# 2_MCU.net
KiCad netlist of a schematic drawn in Altium Designer
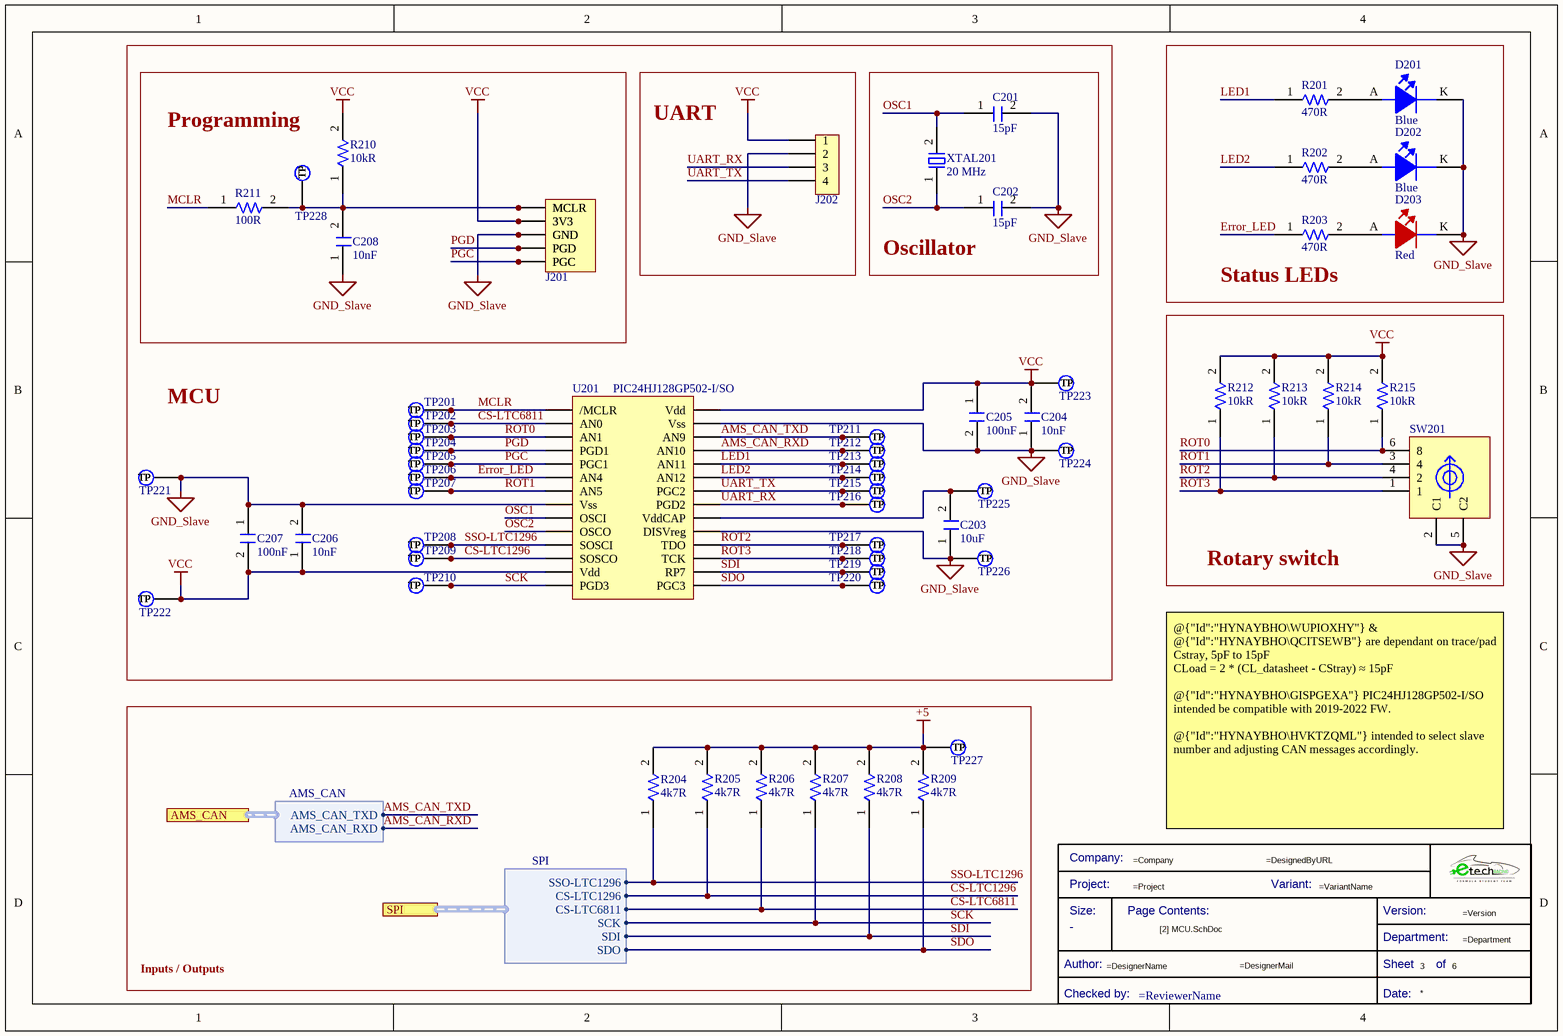
[diagram p0: [2] MCU.SchDoc]

(export (version "E")
  (design (tool "Eeschema 10.0.6"))
  (components
    (comp (ref "*")
      (value "Title Block_template")
      (description "Standard Title Block")
      (fields (field (name "SIZE") "-"))
      (libsource (lib "e-Tech_Racing") (part "Title Block_template"))
    )
    (comp (ref "C201")
      (value "885012007052")
      (footprint "C0805FNPC-R")
      (description "Cap, 15PF, 50V, 5%, C0G/NP0, 0805")
      (fields
        (field (name "TOLERANCE") "5%")
        (field (name "CAPACITANCE") "15pF")
        (field (name ".CREATOR") "DR")
      )
      (libsource (lib "Passives") (part "C15p-50V-0805FNPC-NP0"))
    )
    (comp (ref "C202")
      (value "885012007052")
      (footprint "C0805FNPC-R")
      (description "Cap, 15PF, 50V, 5%, C0G/NP0, 0805")
      (fields
        (field (name "TOLERANCE") "5%")
        (field (name "CAPACITANCE") "15pF")
        (field (name ".CREATOR") "DR")
      )
      (libsource (lib "Passives") (part "C15p-50V-0805FNPC-NP0"))
    )
    (comp (ref "C203")
      (value "885012107014")
      (footprint "C0805FNPC-R")
      (fields (field (name "TOLERANCE") "20%") (field (name "CAPACITANCE") "10uF"))
      (libsource (lib "Passives") (part "C10u-50V-0805FNPC-X7R"))
    )
    (comp (ref "C204")
      (value "885012207092")
      (footprint "C0805FNPC-R")
      (description "Cap, 0.01ΜF, 50V, 10%, X7R, 0805")
      (fields
        (field (name "TOLERANCE") "10%")
        (field (name "CAPACITANCE") "10nF")
        (field (name ".CREATOR") "DR")
      )
      (libsource (lib "Passives") (part "C10n-50V-0805FNPC-X7R"))
    )
    (comp (ref "C205")
      (value "885012207098")
      (footprint "C0805FNPC-R")
      (description "Cap, 0.1ΜF, 50V, 10%, X7R, 0805")
      (fields
        (field (name "TOLERANCE") "10%")
        (field (name "CAPACITANCE") "100nF")
        (field (name ".CREATOR") "DR")
      )
      (libsource (lib "Passives") (part "C100n-50V-0805FNPC-X7R"))
    )
    (comp (ref "C206")
      (value "885012207092")
      (footprint "C0805FNPC-R")
      (description "Cap, 0.01ΜF, 50V, 10%, X7R, 0805")
      (fields
        (field (name "TOLERANCE") "10%")
        (field (name "CAPACITANCE") "10nF")
        (field (name ".CREATOR") "DR")
      )
      (libsource (lib "Passives") (part "C10n-50V-0805FNPC-X7R"))
    )
    (comp (ref "C207")
      (value "885012207098")
      (footprint "C0805FNPC-R")
      (description "Cap, 0.1ΜF, 50V, 10%, X7R, 0805")
      (fields
        (field (name "TOLERANCE") "10%")
        (field (name "CAPACITANCE") "100nF")
        (field (name ".CREATOR") "DR")
      )
      (libsource (lib "Passives") (part "C100n-50V-0805FNPC-X7R"))
    )
    (comp (ref "C208")
      (value "885012207092")
      (footprint "C0805FNPC-R")
      (description "Cap, 0.01ΜF, 50V, 10%, X7R, 0805")
      (fields
        (field (name "TOLERANCE") "10%")
        (field (name "CAPACITANCE") "10nF")
        (field (name ".CREATOR") "DR")
      )
      (libsource (lib "Passives") (part "C10n-50V-0805FNPC-X7R"))
    )
    (comp (ref "D201")
      (value "150080BS75000")
      (footprint "LED_0805_WE")
      (description "LED BLUE CLEAR 0805 SMD")
      (fields (field (name "COLOR") "Blue") (field (name ".CREATOR") "GP"))
      (libsource (lib "Semiconductor") (part "LEDBS-0805-145"))
    )
    (comp (ref "D202")
      (value "150080BS75000")
      (footprint "LED_0805_WE")
      (description "LED BLUE CLEAR 0805 SMD")
      (fields (field (name "COLOR") "Blue") (field (name ".CREATOR") "GP"))
      (libsource (lib "Semiconductor") (part "LEDBS-0805-145"))
    )
    (comp (ref "D203")
      (value "150080RS75000")
      (footprint "LED_0805_WE")
      (description "0805(H=0.8mm) 红色 高亮 λD=625nm VF=2V IF=30mA PD=72mW")
      (fields (field (name "COLOR") "Red") (field (name ".CREATOR") "DR"))
      (libsource (lib "Semiconductor") (part "LEDRS-0805-150"))
    )
    (comp (ref "J201")
      (value "61300511121")
      (footprint "J_PinHeader_1x5")
      (description "THT Vertical Pin Header WR-PHD, Pitch 2.54 mm, Single Row, 5 pins")
      (fields (field (name "MANUFACTURER") "Molex") (field (name ".CREATOR") "GP"))
      (libsource (lib "Electromechanical") (part "J_Pickit3"))
    )
    (comp (ref "J202")
      (value "61300411121")
      (footprint "J_PinHeader_1x4")
      (description "CONN HEADER 4 POS 2.54")
      (fields (field (name ".CREATOR") "AC"))
      (libsource (lib "Electromechanical") (part "J_UART"))
    )
    (comp (ref "R201")
      (value "CR0805-FX-4700GLF")
      (footprint "R0805FTK")
      (description "Res Thick Film 0805 470 Ohm 1% 1/8W ±100ppm/°C Molded SMD SMD Paper Tape on Plastic Reel")
      (fields
        (field (name "TOLERANCE") "1%")
        (field (name "RESISTANCE") "470R")
        (field (name ".CREATOR") "DR")
      )
      (libsource (lib "Passives") (part "R470-0805FTK"))
    )
    (comp (ref "R202")
      (value "CR0805-FX-4700GLF")
      (footprint "R0805FTK")
      (description "Res Thick Film 0805 470 Ohm 1% 1/8W ±100ppm/°C Molded SMD SMD Paper Tape on Plastic Reel")
      (fields
        (field (name "TOLERANCE") "1%")
        (field (name "RESISTANCE") "470R")
        (field (name ".CREATOR") "DR")
      )
      (libsource (lib "Passives") (part "R470-0805FTK"))
    )
    (comp (ref "R203")
      (value "CR0805-FX-4700GLF")
      (footprint "R0805FTK")
      (description "Res Thick Film 0805 470 Ohm 1% 1/8W ±100ppm/°C Molded SMD SMD Paper Tape on Plastic Reel")
      (fields
        (field (name "TOLERANCE") "1%")
        (field (name "RESISTANCE") "470R")
        (field (name ".CREATOR") "DR")
      )
      (libsource (lib "Passives") (part "R470-0805FTK"))
    )
    (comp (ref "R204")
      (value "CR0805-JW-472ELF")
      (footprint "R0805FTK")
      (description "Res Thick Film 0805 4.7K Ohm 5% 1/8W ±200ppm/°C Molded SMD SMD Paper Tape on Plastic Reel")
      (fields
        (field (name "TOLERANCE") "5%")
        (field (name "RESISTANCE") "4k7R")
        (field (name ".CREATOR") "DR")
      )
      (libsource (lib "Passives") (part "R4.7K-0805FTK"))
    )
    (comp (ref "R205")
      (value "CR0805-JW-472ELF")
      (footprint "R0805FTK")
      (description "Res Thick Film 0805 4.7K Ohm 5% 1/8W ±200ppm/°C Molded SMD SMD Paper Tape on Plastic Reel")
      (fields
        (field (name "TOLERANCE") "5%")
        (field (name "RESISTANCE") "4k7R")
        (field (name ".CREATOR") "DR")
      )
      (libsource (lib "Passives") (part "R4.7K-0805FTK"))
    )
    (comp (ref "R206")
      (value "CR0805-JW-472ELF")
      (footprint "R0805FTK")
      (description "Res Thick Film 0805 4.7K Ohm 5% 1/8W ±200ppm/°C Molded SMD SMD Paper Tape on Plastic Reel")
      (fields
        (field (name "TOLERANCE") "5%")
        (field (name "RESISTANCE") "4k7R")
        (field (name ".CREATOR") "DR")
      )
      (libsource (lib "Passives") (part "R4.7K-0805FTK"))
    )
    (comp (ref "R207")
      (value "CR0805-JW-472ELF")
      (footprint "R0805FTK")
      (description "Res Thick Film 0805 4.7K Ohm 5% 1/8W ±200ppm/°C Molded SMD SMD Paper Tape on Plastic Reel")
      (fields
        (field (name "TOLERANCE") "5%")
        (field (name "RESISTANCE") "4k7R")
        (field (name ".CREATOR") "DR")
      )
      (libsource (lib "Passives") (part "R4.7K-0805FTK"))
    )
    (comp (ref "R208")
      (value "CR0805-JW-472ELF")
      (footprint "R0805FTK")
      (description "Res Thick Film 0805 4.7K Ohm 5% 1/8W ±200ppm/°C Molded SMD SMD Paper Tape on Plastic Reel")
      (fields
        (field (name "TOLERANCE") "5%")
        (field (name "RESISTANCE") "4k7R")
        (field (name ".CREATOR") "DR")
      )
      (libsource (lib "Passives") (part "R4.7K-0805FTK"))
    )
    (comp (ref "R209")
      (value "CR0805-JW-472ELF")
      (footprint "R0805FTK")
      (description "Res Thick Film 0805 4.7K Ohm 5% 1/8W ±200ppm/°C Molded SMD SMD Paper Tape on Plastic Reel")
      (fields
        (field (name "TOLERANCE") "5%")
        (field (name "RESISTANCE") "4k7R")
        (field (name ".CREATOR") "DR")
      )
      (libsource (lib "Passives") (part "R4.7K-0805FTK"))
    )
    (comp (ref "R210")
      (value "CR0805-JW-103ELF")
      (footprint "R0805FTK")
      (fields
        (field (name "TOLERANCE") "5%")
        (field (name "RESISTANCE") "10kR")
        (field (name ".CREATOR") "DR")
      )
      (libsource (lib "Passives") (part "R10k-0805FTK"))
    )
    (comp (ref "R211")
      (value "CR0805-FX-1000ELF")
      (footprint "R0805FTK")
      (description "Res Thick Film 0805 100 Ohm 1% 1/8W ±100ppm/°C Molded SMD SMD Paper Tape on Plastic Reel")
      (fields
        (field (name "TOLERANCE") "1%")
        (field (name "RESISTANCE") "100R")
        (field (name ".CREATOR") "DR")
      )
      (libsource (lib "Passives") (part "R100-0805FTK"))
    )
    (comp (ref "R212")
      (value "CR0805-JW-103ELF")
      (footprint "R0805FTK")
      (fields
        (field (name "TOLERANCE") "5%")
        (field (name "RESISTANCE") "10kR")
        (field (name ".CREATOR") "DR")
      )
      (libsource (lib "Passives") (part "R10k-0805FTK"))
    )
    (comp (ref "R213")
      (value "CR0805-JW-103ELF")
      (footprint "R0805FTK")
      (fields
        (field (name "TOLERANCE") "5%")
        (field (name "RESISTANCE") "10kR")
        (field (name ".CREATOR") "DR")
      )
      (libsource (lib "Passives") (part "R10k-0805FTK"))
    )
    (comp (ref "R214")
      (value "CR0805-JW-103ELF")
      (footprint "R0805FTK")
      (fields
        (field (name "TOLERANCE") "5%")
        (field (name "RESISTANCE") "10kR")
        (field (name ".CREATOR") "DR")
      )
      (libsource (lib "Passives") (part "R10k-0805FTK"))
    )
    (comp (ref "R215")
      (value "CR0805-JW-103ELF")
      (footprint "R0805FTK")
      (fields
        (field (name "TOLERANCE") "5%")
        (field (name "RESISTANCE") "10kR")
        (field (name ".CREATOR") "DR")
      )
      (libsource (lib "Passives") (part "R10k-0805FTK"))
    )
    (comp (ref "SW201")
      (value "428542320816")
      (footprint "16RotarySw")
      (description "Switch Rotary DIP Hex 100MA 42V")
      (fields (field (name ".CREATOR") "DR"))
      (libsource (lib "Electromechanical") (part "16RotarySwitch"))
    )
    (comp (ref "TP201")
      (value "TestPoint")
      (footprint "TestPoint")
      (description "Test Point 1x1 mm")
      (fields (field (name ".CREATOR") "GP") (field (name ".PCBCHECK") "GP") (field (name ".SCHCHECK") "GP"))
      (libsource (lib "e-Tech_Racing") (part "TestPoint"))
    )
    (comp (ref "TP202")
      (value "TestPoint")
      (footprint "TestPoint")
      (description "Test Point 1x1 mm")
      (fields (field (name ".CREATOR") "GP") (field (name ".PCBCHECK") "GP") (field (name ".SCHCHECK") "GP"))
      (libsource (lib "e-Tech_Racing") (part "TestPoint"))
    )
    (comp (ref "TP203")
      (value "TestPoint")
      (footprint "TestPoint")
      (description "Test Point 1x1 mm")
      (fields (field (name ".CREATOR") "GP") (field (name ".PCBCHECK") "GP") (field (name ".SCHCHECK") "GP"))
      (libsource (lib "e-Tech_Racing") (part "TestPoint"))
    )
    (comp (ref "TP204")
      (value "TestPoint")
      (footprint "TestPoint")
      (description "Test Point 1x1 mm")
      (fields (field (name ".CREATOR") "GP") (field (name ".PCBCHECK") "GP") (field (name ".SCHCHECK") "GP"))
      (libsource (lib "e-Tech_Racing") (part "TestPoint"))
    )
    (comp (ref "TP205")
      (value "TestPoint")
      (footprint "TestPoint")
      (description "Test Point 1x1 mm")
      (fields (field (name ".CREATOR") "GP") (field (name ".PCBCHECK") "GP") (field (name ".SCHCHECK") "GP"))
      (libsource (lib "e-Tech_Racing") (part "TestPoint"))
    )
    (comp (ref "TP206")
      (value "TestPoint")
      (footprint "TestPoint")
      (description "Test Point 1x1 mm")
      (fields (field (name ".CREATOR") "GP") (field (name ".PCBCHECK") "GP") (field (name ".SCHCHECK") "GP"))
      (libsource (lib "e-Tech_Racing") (part "TestPoint"))
    )
    (comp (ref "TP207")
      (value "TestPoint")
      (footprint "TestPoint")
      (description "Test Point 1x1 mm")
      (fields (field (name ".CREATOR") "GP") (field (name ".PCBCHECK") "GP") (field (name ".SCHCHECK") "GP"))
      (libsource (lib "e-Tech_Racing") (part "TestPoint"))
    )
    (comp (ref "TP208")
      (value "TestPoint")
      (footprint "TestPoint")
      (description "Test Point 1x1 mm")
      (fields (field (name ".CREATOR") "GP") (field (name ".PCBCHECK") "GP") (field (name ".SCHCHECK") "GP"))
      (libsource (lib "e-Tech_Racing") (part "TestPoint"))
    )
    (comp (ref "TP209")
      (value "TestPoint")
      (footprint "TestPoint")
      (description "Test Point 1x1 mm")
      (fields (field (name ".CREATOR") "GP") (field (name ".PCBCHECK") "GP") (field (name ".SCHCHECK") "GP"))
      (libsource (lib "e-Tech_Racing") (part "TestPoint"))
    )
    (comp (ref "TP210")
      (value "TestPoint")
      (footprint "TestPoint")
      (description "Test Point 1x1 mm")
      (fields (field (name ".CREATOR") "GP") (field (name ".PCBCHECK") "GP") (field (name ".SCHCHECK") "GP"))
      (libsource (lib "e-Tech_Racing") (part "TestPoint"))
    )
    (comp (ref "TP211")
      (value "TestPoint")
      (footprint "TestPoint")
      (description "Test Point 1x1 mm")
      (fields (field (name ".CREATOR") "GP") (field (name ".PCBCHECK") "GP") (field (name ".SCHCHECK") "GP"))
      (libsource (lib "e-Tech_Racing") (part "TestPoint"))
    )
    (comp (ref "TP212")
      (value "TestPoint")
      (footprint "TestPoint")
      (description "Test Point 1x1 mm")
      (fields (field (name ".CREATOR") "GP") (field (name ".PCBCHECK") "GP") (field (name ".SCHCHECK") "GP"))
      (libsource (lib "e-Tech_Racing") (part "TestPoint"))
    )
    (comp (ref "TP213")
      (value "TestPoint")
      (footprint "TestPoint")
      (description "Test Point 1x1 mm")
      (fields (field (name ".CREATOR") "GP") (field (name ".PCBCHECK") "GP") (field (name ".SCHCHECK") "GP"))
      (libsource (lib "e-Tech_Racing") (part "TestPoint"))
    )
    (comp (ref "TP214")
      (value "TestPoint")
      (footprint "TestPoint")
      (description "Test Point 1x1 mm")
      (fields (field (name ".CREATOR") "GP") (field (name ".PCBCHECK") "GP") (field (name ".SCHCHECK") "GP"))
      (libsource (lib "e-Tech_Racing") (part "TestPoint"))
    )
    (comp (ref "TP215")
      (value "TestPoint")
      (footprint "TestPoint")
      (description "Test Point 1x1 mm")
      (fields (field (name ".CREATOR") "GP") (field (name ".PCBCHECK") "GP") (field (name ".SCHCHECK") "GP"))
      (libsource (lib "e-Tech_Racing") (part "TestPoint"))
    )
    (comp (ref "TP216")
      (value "TestPoint")
      (footprint "TestPoint")
      (description "Test Point 1x1 mm")
      (fields (field (name ".CREATOR") "GP") (field (name ".PCBCHECK") "GP") (field (name ".SCHCHECK") "GP"))
      (libsource (lib "e-Tech_Racing") (part "TestPoint"))
    )
    (comp (ref "TP217")
      (value "TestPoint")
      (footprint "TestPoint")
      (description "Test Point 1x1 mm")
      (fields (field (name ".CREATOR") "GP") (field (name ".PCBCHECK") "GP") (field (name ".SCHCHECK") "GP"))
      (libsource (lib "e-Tech_Racing") (part "TestPoint"))
    )
    (comp (ref "TP218")
      (value "TestPoint")
      (footprint "TestPoint")
      (description "Test Point 1x1 mm")
      (fields (field (name ".CREATOR") "GP") (field (name ".PCBCHECK") "GP") (field (name ".SCHCHECK") "GP"))
      (libsource (lib "e-Tech_Racing") (part "TestPoint"))
    )
    (comp (ref "TP219")
      (value "TestPoint")
      (footprint "TestPoint")
      (description "Test Point 1x1 mm")
      (fields (field (name ".CREATOR") "GP") (field (name ".PCBCHECK") "GP") (field (name ".SCHCHECK") "GP"))
      (libsource (lib "e-Tech_Racing") (part "TestPoint"))
    )
    (comp (ref "TP220")
      (value "TestPoint")
      (footprint "TestPoint")
      (description "Test Point 1x1 mm")
      (fields (field (name ".CREATOR") "GP") (field (name ".PCBCHECK") "GP") (field (name ".SCHCHECK") "GP"))
      (libsource (lib "e-Tech_Racing") (part "TestPoint"))
    )
    (comp (ref "TP221")
      (value "TestPoint")
      (footprint "TestPoint")
      (description "Test Point 1x1 mm")
      (fields (field (name ".CREATOR") "GP") (field (name ".PCBCHECK") "GP") (field (name ".SCHCHECK") "GP"))
      (libsource (lib "e-Tech_Racing") (part "TestPoint"))
    )
    (comp (ref "TP222")
      (value "TestPoint")
      (footprint "TestPoint")
      (description "Test Point 1x1 mm")
      (fields (field (name ".CREATOR") "GP") (field (name ".PCBCHECK") "GP") (field (name ".SCHCHECK") "GP"))
      (libsource (lib "e-Tech_Racing") (part "TestPoint"))
    )
    (comp (ref "TP223")
      (value "TestPoint")
      (footprint "TestPoint")
      (description "Test Point 1x1 mm")
      (fields (field (name ".CREATOR") "GP") (field (name ".PCBCHECK") "GP") (field (name ".SCHCHECK") "GP"))
      (libsource (lib "e-Tech_Racing") (part "TestPoint"))
    )
    (comp (ref "TP224")
      (value "TestPoint")
      (footprint "TestPoint")
      (description "Test Point 1x1 mm")
      (fields (field (name ".CREATOR") "GP") (field (name ".PCBCHECK") "GP") (field (name ".SCHCHECK") "GP"))
      (libsource (lib "e-Tech_Racing") (part "TestPoint"))
    )
    (comp (ref "TP225")
      (value "TestPoint")
      (footprint "TestPoint")
      (description "Test Point 1x1 mm")
      (fields (field (name ".CREATOR") "GP") (field (name ".PCBCHECK") "GP") (field (name ".SCHCHECK") "GP"))
      (libsource (lib "e-Tech_Racing") (part "TestPoint"))
    )
    (comp (ref "TP226")
      (value "TestPoint")
      (footprint "TestPoint")
      (description "Test Point 1x1 mm")
      (fields (field (name ".CREATOR") "GP") (field (name ".PCBCHECK") "GP") (field (name ".SCHCHECK") "GP"))
      (libsource (lib "e-Tech_Racing") (part "TestPoint"))
    )
    (comp (ref "TP227")
      (value "TestPoint")
      (footprint "TestPoint")
      (description "Test Point 1x1 mm")
      (fields (field (name ".CREATOR") "GP") (field (name ".PCBCHECK") "GP") (field (name ".SCHCHECK") "GP"))
      (libsource (lib "e-Tech_Racing") (part "TestPoint"))
    )
    (comp (ref "TP228")
      (value "TestPoint")
      (footprint "TestPoint")
      (description "Test Point 1x1 mm")
      (fields (field (name ".CREATOR") "GP") (field (name ".PCBCHECK") "GP") (field (name ".SCHCHECK") "GP"))
      (libsource (lib "e-Tech_Racing") (part "TestPoint"))
    )
    (comp (ref "U201")
      (value "PIC24HJ128GP502")
      (footprint "U_PIC24HJ128GP")
      (description "16-bit MCU/DSC, 128 KB, 8192 Bytes, 80 MHz, 3 to 3.6V, SOIC-28, RoHS")
      (fields
        (field (name "MANUFACTURER PART NUMBER 1") "PIC24HJ128GP502-I/SO")
        (field (name ".CREATOR") "DR")
      )
      (libsource (lib "Integrated circuits") (part "U_PIC24HJ128GP502"))
    )
    (comp (ref "XTAL201")
      (value "830028710")
      (footprint "XTAL20M_SMD")
      (description "830028710, 20 MHz")
      (fields
        (field (name "MANUFACTURER") "Würth Elektronik")
        (field (name "FREQUENCY") "20 MHz")
        (field (name ".CREATOR") "GP")
      )
      (libsource (lib "Passives") (part "XTAL20M_SMD"))
    )
  )
  (nets
    (net (code "3") (name "+5") (class "Default")
      (node (ref "R204") (pin "2") (pinfunction "2_2") (pintype "passive"))
      (node (ref "R205") (pin "2") (pinfunction "2_2") (pintype "passive"))
      (node (ref "R206") (pin "2") (pinfunction "2_2") (pintype "passive"))
      (node (ref "R207") (pin "2") (pinfunction "2_2") (pintype "passive"))
      (node (ref "R208") (pin "2") (pinfunction "2_2") (pintype "passive"))
      (node (ref "R209") (pin "2") (pinfunction "2_2") (pintype "passive"))
      (node (ref "TP227") (pin "1") (pinfunction "TP_1") (pintype "passive"))
    )
    (net (code "4") (name "/AMS_CAN_RXD") (class "Default")
      (node (ref "TP212") (pin "1") (pinfunction "TP_1") (pintype "passive"))
      (node (ref "U201") (pin "25") (pinfunction "AN10_25") (pintype "passive"))
    )
    (net (code "5") (name "/AMS_CAN_TXD") (class "Default")
      (node (ref "TP211") (pin "1") (pinfunction "TP_1") (pintype "passive"))
      (node (ref "U201") (pin "26") (pinfunction "AN9_26") (pintype "passive"))
    )
    (net (code "6") (name "/CS-LTC1296") (class "Default")
      (node (ref "R205") (pin "1") (pinfunction "1_1") (pintype "passive"))
      (node (ref "TP209") (pin "1") (pinfunction "TP_1") (pintype "passive"))
      (node (ref "U201") (pin "12") (pinfunction "SOSCO_12") (pintype "passive"))
    )
    (net (code "7") (name "/CS-LTC6811") (class "Default")
      (node (ref "R206") (pin "1") (pinfunction "1_1") (pintype "passive"))
      (node (ref "TP202") (pin "1") (pinfunction "TP_1") (pintype "passive"))
      (node (ref "U201") (pin "2") (pinfunction "AN0_2") (pintype "passive"))
    )
    (net (code "8") (name "/Error_LED") (class "Default")
      (node (ref "R203") (pin "1") (pinfunction "1_1") (pintype "passive"))
      (node (ref "TP206") (pin "1") (pinfunction "TP_1") (pintype "passive"))
      (node (ref "U201") (pin "6") (pinfunction "AN4_6") (pintype "passive"))
    )
    (net (code "9") (name "/LED1") (class "Default")
      (node (ref "R201") (pin "1") (pinfunction "1_1") (pintype "passive"))
      (node (ref "TP213") (pin "1") (pinfunction "TP_1") (pintype "passive"))
      (node (ref "U201") (pin "24") (pinfunction "AN11_24") (pintype "passive"))
    )
    (net (code "10") (name "/LED2") (class "Default")
      (node (ref "R202") (pin "1") (pinfunction "1_1") (pintype "passive"))
      (node (ref "TP214") (pin "1") (pinfunction "TP_1") (pintype "passive"))
      (node (ref "U201") (pin "23") (pinfunction "AN12_23") (pintype "passive"))
    )
    (net (code "11") (name "/MCLR") (class "Default")
      (node (ref "R211") (pin "1") (pinfunction "1_1") (pintype "passive"))
      (node (ref "TP201") (pin "1") (pinfunction "TP_1") (pintype "passive"))
      (node (ref "U201") (pin "1") (pinfunction "/MCLR_1") (pintype "passive"))
    )
    (net (code "12") (name "/OSC1") (class "Default")
      (node (ref "C201") (pin "1") (pinfunction "1_1") (pintype "passive"))
      (node (ref "U201") (pin "9") (pinfunction "OSCI_9") (pintype "passive"))
      (node (ref "XTAL201") (pin "2") (pinfunction "2_2") (pintype "passive"))
    )
    (net (code "13") (name "/OSC2") (class "Default")
      (node (ref "C202") (pin "1") (pinfunction "1_1") (pintype "passive"))
      (node (ref "U201") (pin "10") (pinfunction "OSCO_10") (pintype "passive"))
      (node (ref "XTAL201") (pin "1") (pinfunction "1_1") (pintype "passive"))
    )
    (net (code "14") (name "/PGC") (class "Default")
      (node (ref "J201") (pin "5") (pinfunction "PGC_5") (pintype "passive"))
      (node (ref "TP205") (pin "1") (pinfunction "TP_1") (pintype "passive"))
      (node (ref "U201") (pin "5") (pinfunction "PGC1_5") (pintype "passive"))
    )
    (net (code "15") (name "/PGD") (class "Default")
      (node (ref "J201") (pin "4") (pinfunction "PGD_4") (pintype "passive"))
      (node (ref "TP204") (pin "1") (pinfunction "TP_1") (pintype "passive"))
      (node (ref "U201") (pin "4") (pinfunction "PGD1_4") (pintype "passive"))
    )
    (net (code "16") (name "/ROT0") (class "Default")
      (node (ref "R215") (pin "1") (pinfunction "1_1") (pintype "passive"))
      (node (ref "SW201") (pin "6") (pinfunction "8_6") (pintype "passive"))
      (node (ref "TP203") (pin "1") (pinfunction "TP_1") (pintype "passive"))
      (node (ref "U201") (pin "3") (pinfunction "AN1_3") (pintype "passive"))
    )
    (net (code "17") (name "/ROT1") (class "Default")
      (node (ref "R214") (pin "1") (pinfunction "1_1") (pintype "passive"))
      (node (ref "SW201") (pin "3") (pinfunction "4_3") (pintype "passive"))
      (node (ref "TP207") (pin "1") (pinfunction "TP_1") (pintype "passive"))
      (node (ref "U201") (pin "7") (pinfunction "AN5_7") (pintype "passive"))
    )
    (net (code "18") (name "/ROT2") (class "Default")
      (node (ref "R213") (pin "1") (pinfunction "1_1") (pintype "passive"))
      (node (ref "SW201") (pin "4") (pinfunction "2_4") (pintype "passive"))
      (node (ref "TP217") (pin "1") (pinfunction "TP_1") (pintype "passive"))
      (node (ref "U201") (pin "18") (pinfunction "TDO_18") (pintype "passive"))
    )
    (net (code "19") (name "/ROT3") (class "Default")
      (node (ref "R212") (pin "1") (pinfunction "1_1") (pintype "passive"))
      (node (ref "SW201") (pin "1") (pinfunction "1_1") (pintype "passive"))
      (node (ref "TP218") (pin "1") (pinfunction "TP_1") (pintype "passive"))
      (node (ref "U201") (pin "17") (pinfunction "TCK_17") (pintype "passive"))
    )
    (net (code "20") (name "/SCK") (class "Default")
      (node (ref "R207") (pin "1") (pinfunction "1_1") (pintype "passive"))
      (node (ref "TP210") (pin "1") (pinfunction "TP_1") (pintype "passive"))
      (node (ref "U201") (pin "14") (pinfunction "PGD3_14") (pintype "passive"))
    )
    (net (code "21") (name "/SDI") (class "Default")
      (node (ref "R208") (pin "1") (pinfunction "1_1") (pintype "passive"))
      (node (ref "TP219") (pin "1") (pinfunction "TP_1") (pintype "passive"))
      (node (ref "U201") (pin "16") (pinfunction "RP7_16") (pintype "passive"))
    )
    (net (code "22") (name "/SDO") (class "Default")
      (node (ref "R209") (pin "1") (pinfunction "1_1") (pintype "passive"))
      (node (ref "TP220") (pin "1") (pinfunction "TP_1") (pintype "passive"))
      (node (ref "U201") (pin "15") (pinfunction "PGC3_15") (pintype "passive"))
    )
    (net (code "23") (name "/SSO-LTC1296") (class "Default")
      (node (ref "R204") (pin "1") (pinfunction "1_1") (pintype "passive"))
      (node (ref "TP208") (pin "1") (pinfunction "TP_1") (pintype "passive"))
      (node (ref "U201") (pin "11") (pinfunction "SOSCI_11") (pintype "passive"))
    )
    (net (code "24") (name "/UART_RX") (class "Default")
      (node (ref "J202") (pin "3") (pinfunction "3_3") (pintype "passive"))
      (node (ref "TP216") (pin "1") (pinfunction "TP_1") (pintype "passive"))
      (node (ref "U201") (pin "21") (pinfunction "PGD2_21") (pintype "passive"))
    )
    (net (code "25") (name "/UART_TX") (class "Default")
      (node (ref "J202") (pin "4") (pinfunction "4_4") (pintype "passive"))
      (node (ref "TP215") (pin "1") (pinfunction "TP_1") (pintype "passive"))
      (node (ref "U201") (pin "22") (pinfunction "PGC2_22") (pintype "passive"))
    )
    (net (code "28") (name "GND_Slave") (class "Default")
      (node (ref "C201") (pin "2") (pinfunction "2_2") (pintype "passive"))
      (node (ref "C202") (pin "2") (pinfunction "2_2") (pintype "passive"))
      (node (ref "C203") (pin "1") (pinfunction "1_1") (pintype "passive"))
      (node (ref "C204") (pin "1") (pinfunction "1_1") (pintype "passive"))
      (node (ref "C205") (pin "2") (pinfunction "2_2") (pintype "passive"))
      (node (ref "C206") (pin "2") (pinfunction "2_2") (pintype "passive"))
      (node (ref "C207") (pin "1") (pinfunction "1_1") (pintype "passive"))
      (node (ref "C208") (pin "1") (pinfunction "1_1") (pintype "passive"))
      (node (ref "D201") (pin "K") (pinfunction "K_K") (pintype "passive"))
      (node (ref "D202") (pin "K") (pinfunction "K_K") (pintype "passive"))
      (node (ref "D203") (pin "K") (pinfunction "K_K") (pintype "passive"))
      (node (ref "J201") (pin "3") (pinfunction "GND_3") (pintype "passive"))
      (node (ref "J202") (pin "2") (pinfunction "2_2") (pintype "passive"))
      (node (ref "SW201") (pin "2") (pinfunction "C1_2") (pintype "passive"))
      (node (ref "SW201") (pin "5") (pinfunction "C2_5") (pintype "passive"))
      (node (ref "TP221") (pin "1") (pinfunction "TP_1") (pintype "passive"))
      (node (ref "TP224") (pin "1") (pinfunction "TP_1") (pintype "passive"))
      (node (ref "TP226") (pin "1") (pinfunction "TP_1") (pintype "passive"))
      (node (ref "U201") (pin "19") (pinfunction "DISVreg_19") (pintype "passive"))
      (node (ref "U201") (pin "27") (pinfunction "Vss_27") (pintype "passive"))
      (node (ref "U201") (pin "8") (pinfunction "Vss_8") (pintype "passive"))
    )
    (net (code "29") (name "Net-(D201-PadA)") (class "Default")
      (node (ref "D201") (pin "A") (pinfunction "A_A") (pintype "passive"))
      (node (ref "R201") (pin "2") (pinfunction "2_2") (pintype "passive"))
    )
    (net (code "30") (name "Net-(D202-PadA)") (class "Default")
      (node (ref "D202") (pin "A") (pinfunction "A_A") (pintype "passive"))
      (node (ref "R202") (pin "2") (pinfunction "2_2") (pintype "passive"))
    )
    (net (code "31") (name "Net-(D203-PadA)") (class "Default")
      (node (ref "D203") (pin "A") (pinfunction "A_A") (pintype "passive"))
      (node (ref "R203") (pin "2") (pinfunction "2_2") (pintype "passive"))
    )
    (net (code "32") (name "Net-(J201-MCLR)") (class "Default")
      (node (ref "C208") (pin "2") (pinfunction "2_2") (pintype "passive"))
      (node (ref "J201") (pin "1") (pinfunction "MCLR_1") (pintype "passive"))
      (node (ref "R210") (pin "1") (pinfunction "1_1") (pintype "passive"))
      (node (ref "R211") (pin "2") (pinfunction "2_2") (pintype "passive"))
      (node (ref "TP228") (pin "1") (pinfunction "TP_1") (pintype "passive"))
    )
    (net (code "33") (name "Net-(TP225-TP)") (class "Default")
      (node (ref "C203") (pin "2") (pinfunction "2_2") (pintype "passive"))
      (node (ref "TP225") (pin "1") (pinfunction "TP_1") (pintype "passive"))
      (node (ref "U201") (pin "20") (pinfunction "VddCAP_20") (pintype "passive"))
    )
    (net (code "34") (name "VCC") (class "Default")
      (node (ref "C204") (pin "2") (pinfunction "2_2") (pintype "passive"))
      (node (ref "C205") (pin "1") (pinfunction "1_1") (pintype "passive"))
      (node (ref "C206") (pin "1") (pinfunction "1_1") (pintype "passive"))
      (node (ref "C207") (pin "2") (pinfunction "2_2") (pintype "passive"))
      (node (ref "J201") (pin "2") (pinfunction "3V3_2") (pintype "passive"))
      (node (ref "J202") (pin "1") (pinfunction "1_1") (pintype "passive"))
      (node (ref "R210") (pin "2") (pinfunction "2_2") (pintype "passive"))
      (node (ref "R212") (pin "2") (pinfunction "2_2") (pintype "passive"))
      (node (ref "R213") (pin "2") (pinfunction "2_2") (pintype "passive"))
      (node (ref "R214") (pin "2") (pinfunction "2_2") (pintype "passive"))
      (node (ref "R215") (pin "2") (pinfunction "2_2") (pintype "passive"))
      (node (ref "TP222") (pin "1") (pinfunction "TP_1") (pintype "passive"))
      (node (ref "TP223") (pin "1") (pinfunction "TP_1") (pintype "passive"))
      (node (ref "U201") (pin "13") (pinfunction "Vdd_13") (pintype "passive"))
      (node (ref "U201") (pin "28") (pinfunction "Vdd_28") (pintype "passive"))
    )
  )
)
